# AquariumComputer.net
KiCad netlist of a schematic drawn in EAGLE
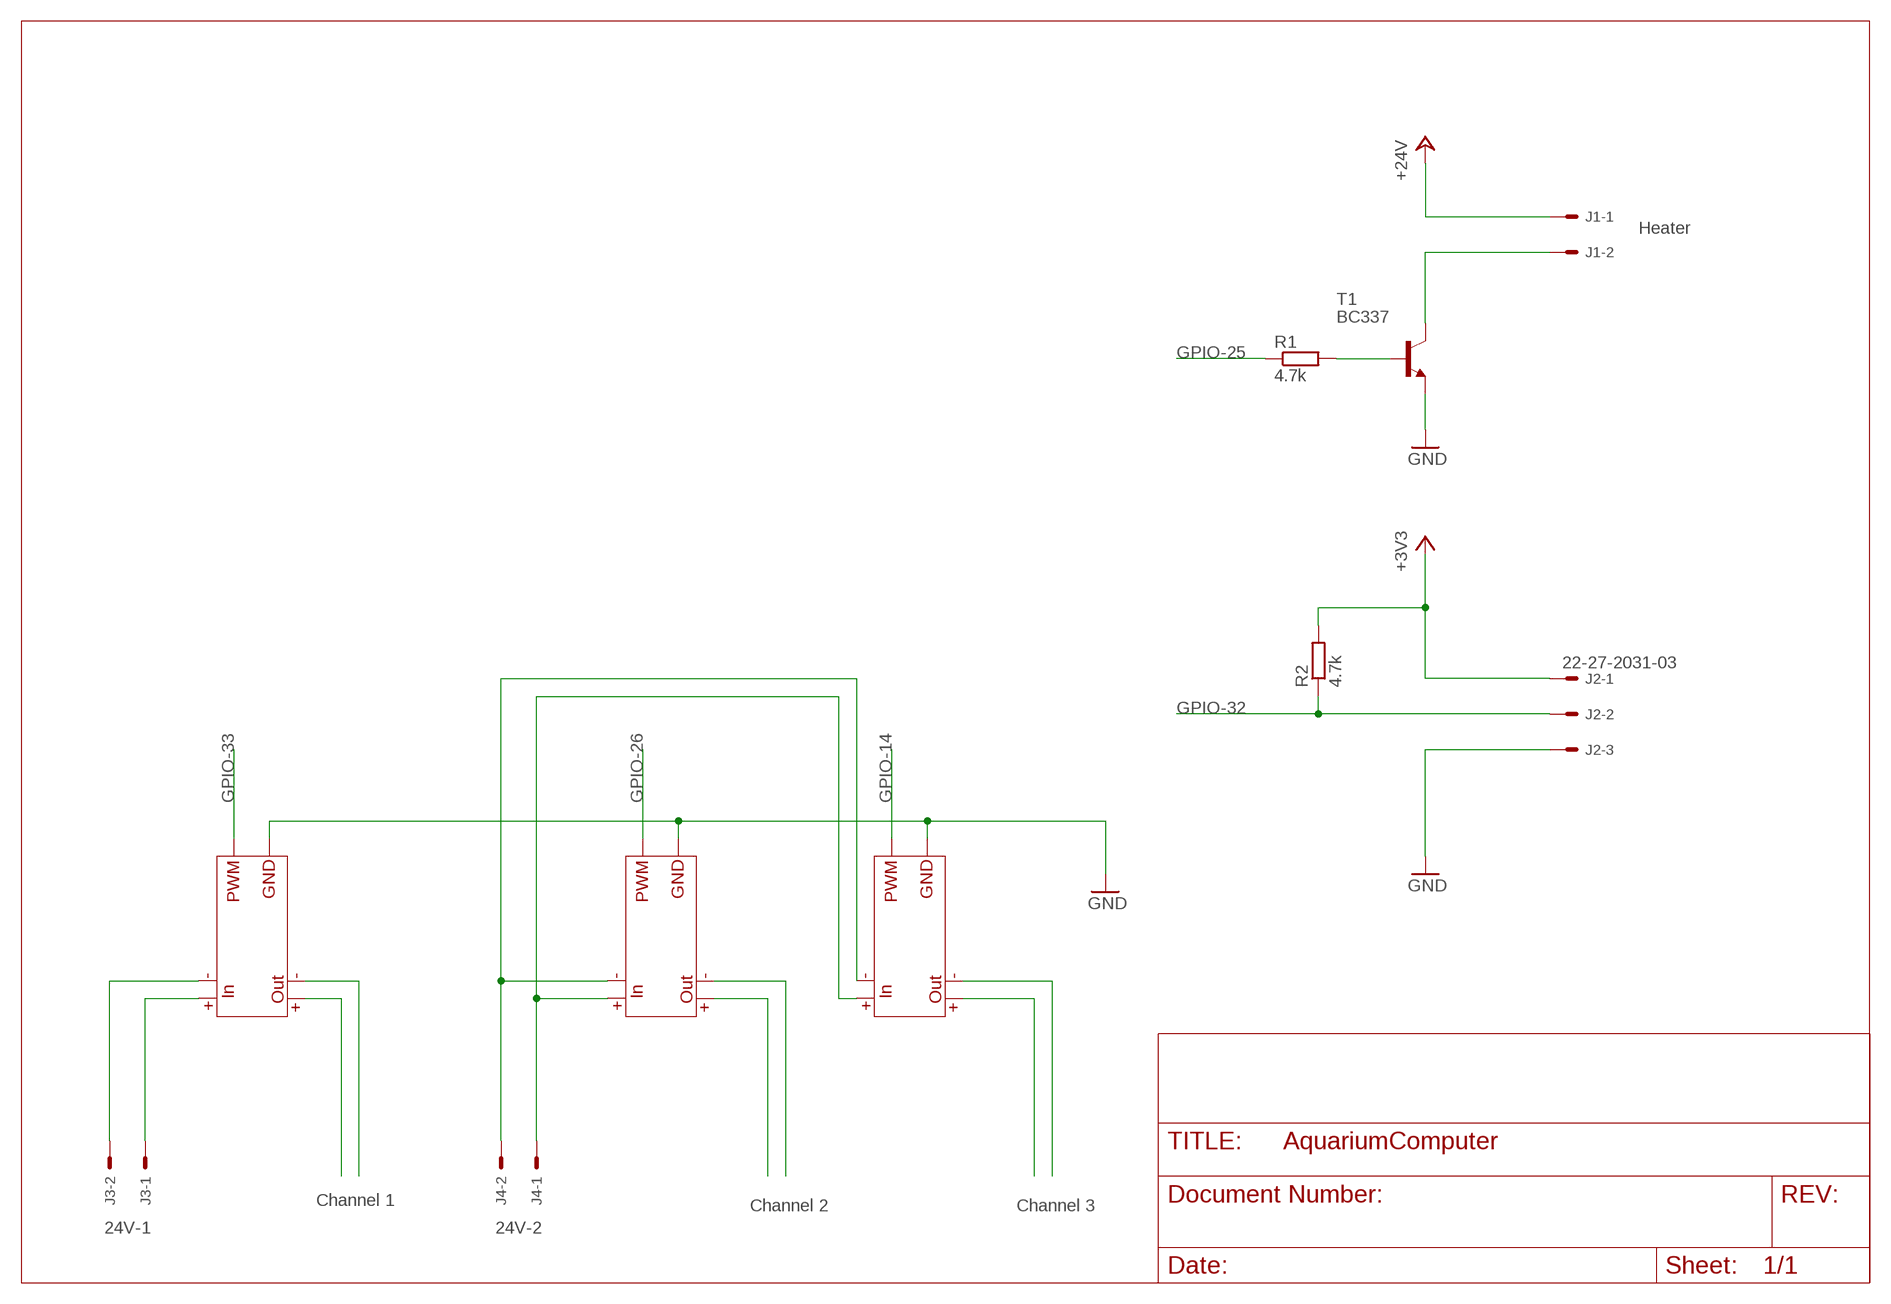
[diagram p0: schematic, sheet 1]

(export (version "E")
  (design (tool "Eeschema 10.0.6"))
  (components
    (comp (ref "J1")
      (value "22-05-7028-02")
      (footprint "eagle-import:7395-02")
      (fields (field (name "MF") "MOLEX"))
      (libsource (lib "eagle-import") (part "22-?-0205-7028"))
    )
    (comp (ref "J2")
      (value "22-27-2031-03")
      (footprint "eagle-import:6410-03")
      (fields (field (name "MF") "MOLEX"))
      (libsource (lib "eagle-import") (part "22-?-0327-2031"))
    )
    (comp (ref "J3")
      (value "24V-1")
      (footprint "eagle-import:7395-02")
      (fields (field (name "MF") "MOLEX"))
      (libsource (lib "eagle-import") (part "22-?-0205-7028"))
    )
    (comp (ref "J4")
      (value "24V-2")
      (footprint "eagle-import:7395-02")
      (fields (field (name "MF") "MOLEX"))
      (libsource (lib "eagle-import") (part "22-?-0205-7028"))
    )
    (comp (ref "R1")
      (value "4.7k")
      (footprint "eagle-import:0207_12")
      (libsource (lib "eagle-import") (part "R-EU_0207/12"))
    )
    (comp (ref "R2")
      (value "4.7k")
      (footprint "eagle-import:0207_12")
      (libsource (lib "eagle-import") (part "R-EU_0207/12"))
    )
    (comp (ref "T1")
      (value "BC337")
      (footprint "eagle-import:TO92")
      (libsource (lib "eagle-import") (part "BC337"))
    )
  )
  (nets
    (net (code "1") (name "+3V3") (class "Default")
      (node (ref "J2") (pin "1") (pinfunction "S_1") (pintype "passive"))
      (node (ref "R2") (pin "2") (pinfunction "2_2") (pintype "passive"))
    )
    (net (code "2") (name "+24V") (class "Default")
      (node (ref "J1") (pin "1") (pinfunction "S_1") (pintype "passive"))
    )
    (net (code "4") (name "/GPIO-25") (class "Default")
      (node (ref "R1") (pin "1") (pinfunction "1_1") (pintype "passive"))
    )
    (net (code "6") (name "/GPIO-32") (class "Default")
      (node (ref "J2") (pin "2") (pinfunction "S_2") (pintype "passive"))
      (node (ref "R2") (pin "1") (pinfunction "1_1") (pintype "passive"))
    )
    (net (code "8") (name "GND") (class "Default")
      (node (ref "J2") (pin "3") (pinfunction "S_3") (pintype "passive"))
      (node (ref "T1") (pin "1") (pinfunction "E_1") (pintype "passive"))
    )
    (net (code "9") (name "Net-(J1B-S)") (class "Default")
      (node (ref "J1") (pin "2") (pinfunction "S_2") (pintype "passive"))
      (node (ref "T1") (pin "3") (pinfunction "C_3") (pintype "passive"))
    )
    (net (code "10") (name "Net-(T1-B)") (class "Default")
      (node (ref "R1") (pin "2") (pinfunction "2_2") (pintype "passive"))
      (node (ref "T1") (pin "2") (pinfunction "B_2") (pintype "passive"))
    )
    (net (code "11") (name "unconnected-(J3A-S-Pad1)") (class "Default")
      (node (ref "J3") (pin "1") (pinfunction "S_1") (pintype "passive"))
    )
    (net (code "12") (name "unconnected-(J3B-S-Pad2)") (class "Default")
      (node (ref "J3") (pin "2") (pinfunction "S_2") (pintype "passive"))
    )
    (net (code "13") (name "unconnected-(J4A-S-Pad1)") (class "Default")
      (node (ref "J4") (pin "1") (pinfunction "S_1") (pintype "passive"))
    )
    (net (code "14") (name "unconnected-(J4B-S-Pad2)") (class "Default")
      (node (ref "J4") (pin "2") (pinfunction "S_2") (pintype "passive"))
    )
  )
)
